# stm32-dip40.net
KiCad netlist of a schematic drawn in EAGLE
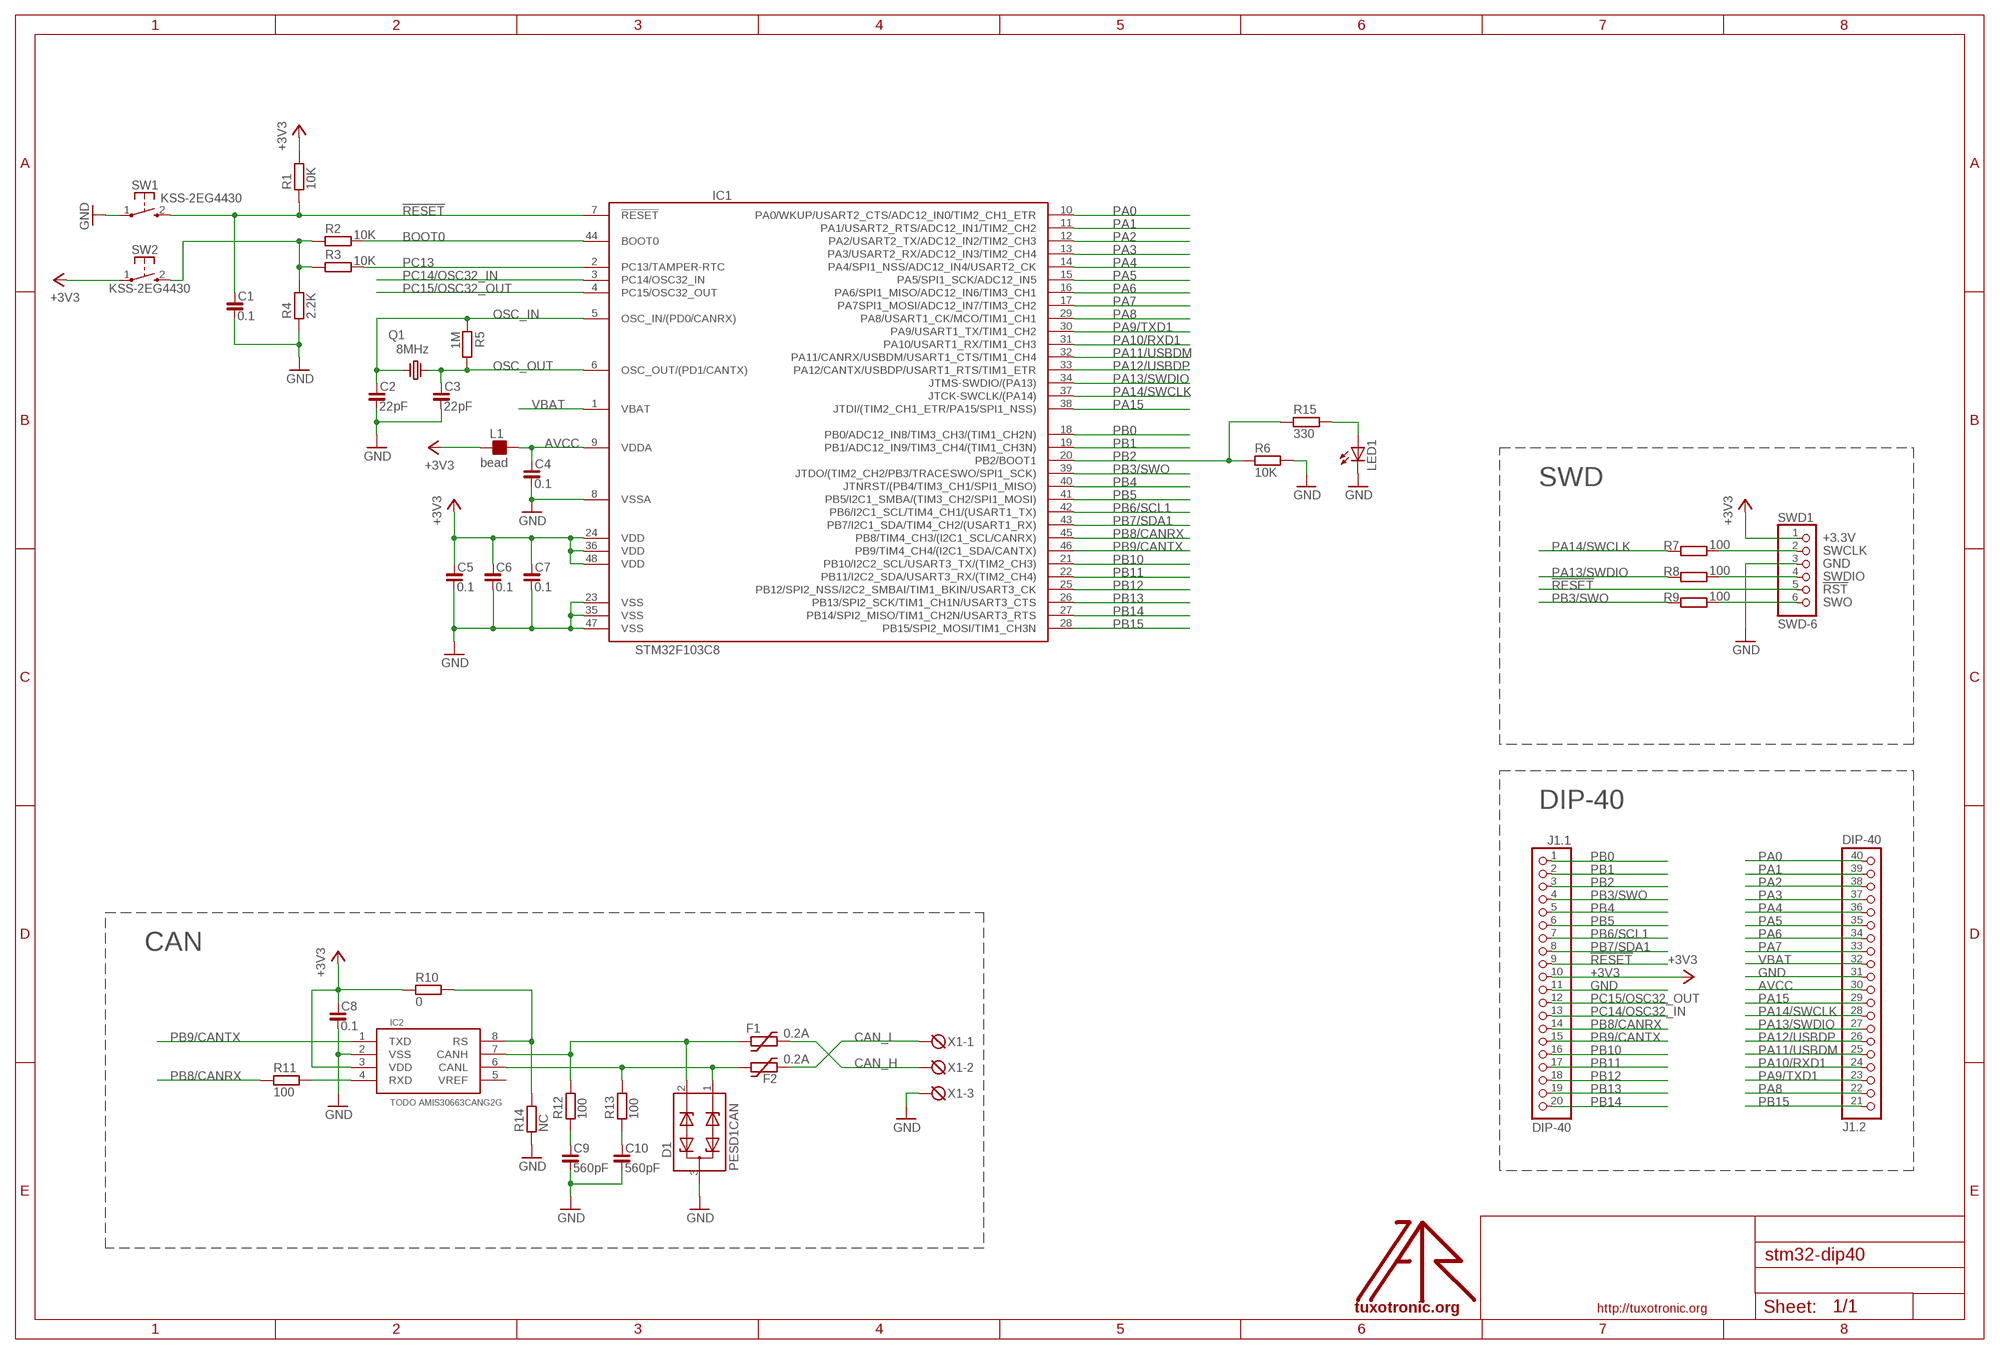
[diagram p0: schematic, sheet 1]

(export (version "E")
  (design (tool "Eeschema 10.0.6"))
  (components
    (comp (ref "C1")
      (value "0.1")
      (footprint "eagle-import:C0603")
      (libsource (lib "eagle-import") (part "C_0603"))
    )
    (comp (ref "C2")
      (value "22pF")
      (footprint "eagle-import:C0603")
      (libsource (lib "eagle-import") (part "C_0603"))
    )
    (comp (ref "C3")
      (value "22pF")
      (footprint "eagle-import:C0603")
      (libsource (lib "eagle-import") (part "C_0603"))
    )
    (comp (ref "C4")
      (value "0.1")
      (footprint "eagle-import:C0603")
      (libsource (lib "eagle-import") (part "C_0603"))
    )
    (comp (ref "C5")
      (value "0.1")
      (footprint "eagle-import:C0603")
      (libsource (lib "eagle-import") (part "C_0603"))
    )
    (comp (ref "C6")
      (value "0.1")
      (footprint "eagle-import:C0603")
      (libsource (lib "eagle-import") (part "C_0603"))
    )
    (comp (ref "C7")
      (value "0.1")
      (footprint "eagle-import:C0603")
      (libsource (lib "eagle-import") (part "C_0603"))
    )
    (comp (ref "C8")
      (value "0.1")
      (footprint "eagle-import:C0603")
      (libsource (lib "eagle-import") (part "C_0603"))
    )
    (comp (ref "C9")
      (value "560pF")
      (footprint "eagle-import:C0603")
      (libsource (lib "eagle-import") (part "C_0603"))
    )
    (comp (ref "C10")
      (value "560pF")
      (footprint "eagle-import:C0603")
      (libsource (lib "eagle-import") (part "C_0603"))
    )
    (comp (ref "D1")
      (value "PESD1CAN")
      (footprint "eagle-import:SOT23")
      (libsource (lib "eagle-import") (part "PESD1CAN"))
    )
    (comp (ref "F1")
      (value "0.2A")
      (footprint "eagle-import:1206L")
      (libsource (lib "eagle-import") (part "1206L"))
    )
    (comp (ref "F2")
      (value "0.2A")
      (footprint "eagle-import:1206L")
      (libsource (lib "eagle-import") (part "1206L"))
    )
    (comp (ref "IC1")
      (value "STM32F103C8")
      (footprint "eagle-import:LQFP48")
      (libsource (lib "eagle-import") (part "STM32F103C8"))
    )
    (comp (ref "IC2")
      (value "TODO AMIS30663CANG2G")
      (footprint "eagle-import:SO08")
      (libsource (lib "eagle-import") (part "SN65HVD230"))
    )
    (comp (ref "J1")
      (value "DIP-40")
      (footprint "eagle-import:DIP-40")
      (libsource (lib "eagle-import") (part "DIP-40"))
    )
    (comp (ref "L1")
      (value "bead")
      (footprint "eagle-import:L0603")
      (libsource (lib "eagle-import") (part "FB_0603"))
    )
    (comp (ref "LED1")
      (value "LEDCHIPLED_0603")
      (footprint "eagle-import:CHIPLED_0603")
      (libsource (lib "eagle-import") (part "LEDCHIPLED_0603"))
    )
    (comp (ref "Q1")
      (value "8MHz")
      (footprint "eagle-import:HC49_S")
      (libsource (lib "eagle-import") (part "CRYSTAL-HC49S"))
    )
    (comp (ref "R1")
      (value "10K")
      (footprint "eagle-import:R0603")
      (libsource (lib "eagle-import") (part "R_0603"))
    )
    (comp (ref "R2")
      (value "10K")
      (footprint "eagle-import:R0603")
      (libsource (lib "eagle-import") (part "R_0603"))
    )
    (comp (ref "R3")
      (value "10K")
      (footprint "eagle-import:R0603")
      (libsource (lib "eagle-import") (part "R_0603"))
    )
    (comp (ref "R4")
      (value "2.2K")
      (footprint "eagle-import:R0603")
      (libsource (lib "eagle-import") (part "R_0603"))
    )
    (comp (ref "R5")
      (value "1M")
      (footprint "eagle-import:R0603")
      (libsource (lib "eagle-import") (part "R_0603"))
    )
    (comp (ref "R6")
      (value "10K")
      (footprint "eagle-import:R0603")
      (libsource (lib "eagle-import") (part "R_0603"))
    )
    (comp (ref "R7")
      (value "100")
      (footprint "eagle-import:R0603")
      (libsource (lib "eagle-import") (part "R_0603"))
    )
    (comp (ref "R8")
      (value "100")
      (footprint "eagle-import:R0603")
      (libsource (lib "eagle-import") (part "R_0603"))
    )
    (comp (ref "R9")
      (value "100")
      (footprint "eagle-import:R0603")
      (libsource (lib "eagle-import") (part "R_0603"))
    )
    (comp (ref "R10")
      (value "0")
      (footprint "eagle-import:R0603")
      (libsource (lib "eagle-import") (part "R_0603"))
    )
    (comp (ref "R11")
      (value "100")
      (footprint "eagle-import:R0603")
      (libsource (lib "eagle-import") (part "R_0603"))
    )
    (comp (ref "R12")
      (value "100")
      (footprint "eagle-import:R0603")
      (libsource (lib "eagle-import") (part "R_0603"))
    )
    (comp (ref "R13")
      (value "100")
      (footprint "eagle-import:R0603")
      (libsource (lib "eagle-import") (part "R_0603"))
    )
    (comp (ref "R14")
      (value "NC")
      (footprint "eagle-import:R0603")
      (libsource (lib "eagle-import") (part "R_0603"))
    )
    (comp (ref "R15")
      (value "330")
      (footprint "eagle-import:R0603")
      (libsource (lib "eagle-import") (part "R_0603"))
    )
    (comp (ref "SW1")
      (value "KSS-2EG4430")
      (footprint "eagle-import:KSS-2EG4430")
      (libsource (lib "eagle-import") (part "KSS-2EG4430"))
    )
    (comp (ref "SW2")
      (value "KSS-2EG4430")
      (footprint "eagle-import:KSS-2EG4430")
      (libsource (lib "eagle-import") (part "KSS-2EG4430"))
    )
    (comp (ref "SWD1")
      (value "SWD-6")
      (footprint "eagle-import:JTAG6PIN")
      (libsource (lib "eagle-import") (part "SWD-6"))
    )
    (comp (ref "U$")
      (value "LOGO")
      (footprint "eagle-import:TT_LOGO")
      (libsource (lib "eagle-import") (part "LOGO"))
    )
    (comp (ref "X1")
      (value "DG3XX-03-3.5")
      (footprint "eagle-import:DG350-3.5-03P")
      (libsource (lib "eagle-import") (part "DG3XX-03-3.5"))
    )
  )
  (nets
    (net (code "1") (name "+3V3") (class "Default")
      (node (ref "C5") (pin "1") (pinfunction "1_1") (pintype "passive"))
      (node (ref "C6") (pin "1") (pinfunction "1_1") (pintype "passive"))
      (node (ref "C7") (pin "1") (pinfunction "1_1") (pintype "passive"))
      (node (ref "C8") (pin "1") (pinfunction "1_1") (pintype "passive"))
      (node (ref "IC1") (pin "24") (pinfunction "VDD_24") (pintype "power_in"))
      (node (ref "IC1") (pin "36") (pinfunction "VDD_36") (pintype "power_in"))
      (node (ref "IC1") (pin "48") (pinfunction "VDD_48") (pintype "power_in"))
      (node (ref "IC2") (pin "3") (pinfunction "VDD_3") (pintype "power_in"))
      (node (ref "J1") (pin "10") (pinfunction "10_10") (pintype "passive"))
      (node (ref "L1") (pin "1") (pinfunction "1_1") (pintype "passive"))
      (node (ref "R1") (pin "2") (pinfunction "2_2") (pintype "passive"))
      (node (ref "R10") (pin "1") (pinfunction "1_1") (pintype "passive"))
      (node (ref "SW2") (pin "1") (pinfunction "P_1") (pintype "passive"))
      (node (ref "SWD1") (pin "1") (pinfunction "1_1") (pintype "passive"))
    )
    (net (code "2") (name "/AVCC") (class "Default")
      (node (ref "C4") (pin "1") (pinfunction "1_1") (pintype "passive"))
      (node (ref "IC1") (pin "9") (pinfunction "VDDA_9") (pintype "power_in"))
      (node (ref "J1") (pin "30") (pinfunction "10_30") (pintype "passive"))
      (node (ref "L1") (pin "2") (pinfunction "2_2") (pintype "passive"))
    )
    (net (code "3") (name "/BOOT0") (class "Default")
      (node (ref "IC1") (pin "44") (pinfunction "BOOT0_44") (pintype "input"))
      (node (ref "R2") (pin "2") (pinfunction "2_2") (pintype "passive"))
    )
    (net (code "4") (name "/CAN_H") (class "Default")
      (node (ref "F1") (pin "P$2") (pinfunction "2_P$2") (pintype "passive"))
      (node (ref "X1") (pin "2") (pinfunction "KL_2") (pintype "passive"))
    )
    (net (code "5") (name "/CAN_L") (class "Default")
      (node (ref "F2") (pin "P$2") (pinfunction "2_P$2") (pintype "passive"))
      (node (ref "X1") (pin "1") (pinfunction "KL_1") (pintype "passive"))
    )
    (net (code "6") (name "/OSC_IN") (class "Default")
      (node (ref "C2") (pin "1") (pinfunction "1_1") (pintype "passive"))
      (node (ref "IC1") (pin "5") (pinfunction "OSC_IN/(PD0/CANRX)_5") (pintype "input"))
      (node (ref "Q1") (pin "1") (pinfunction "1_1") (pintype "passive"))
      (node (ref "R5") (pin "1") (pinfunction "1_1") (pintype "passive"))
    )
    (net (code "7") (name "/OSC_OUT") (class "Default")
      (node (ref "C3") (pin "1") (pinfunction "1_1") (pintype "passive"))
      (node (ref "IC1") (pin "6") (pinfunction "OSC_OUT/(PD1/CANTX)_6") (pintype "output"))
      (node (ref "Q1") (pin "2") (pinfunction "2_2") (pintype "passive"))
      (node (ref "R5") (pin "2") (pinfunction "2_2") (pintype "passive"))
    )
    (net (code "8") (name "/PA0") (class "Default")
      (node (ref "IC1") (pin "10") (pinfunction "PA0/WKUP/USART2_CTS/ADC12_IN0/TIM2_CH1_ETR_10") (pintype "bidirectional"))
      (node (ref "J1") (pin "40") (pinfunction "20_40") (pintype "passive"))
    )
    (net (code "9") (name "/PA1") (class "Default")
      (node (ref "IC1") (pin "11") (pinfunction "PA1/USART2_RTS/ADC12_IN1/TIM2_CH2_11") (pintype "bidirectional"))
      (node (ref "J1") (pin "39") (pinfunction "19_39") (pintype "passive"))
    )
    (net (code "10") (name "/PA2") (class "Default")
      (node (ref "IC1") (pin "12") (pinfunction "PA2/USART2_TX/ADC12_IN2/TIM2_CH3_12") (pintype "bidirectional"))
      (node (ref "J1") (pin "38") (pinfunction "18_38") (pintype "passive"))
    )
    (net (code "11") (name "/PA3") (class "Default")
      (node (ref "IC1") (pin "13") (pinfunction "PA3/USART2_RX/ADC12_IN3/TIM2_CH4_13") (pintype "bidirectional"))
      (node (ref "J1") (pin "37") (pinfunction "17_37") (pintype "passive"))
    )
    (net (code "12") (name "/PA4") (class "Default")
      (node (ref "IC1") (pin "14") (pinfunction "PA4/SPI1_NSS/ADC12_IN4/USART2_CK_14") (pintype "bidirectional"))
      (node (ref "J1") (pin "36") (pinfunction "16_36") (pintype "passive"))
    )
    (net (code "13") (name "/PA5") (class "Default")
      (node (ref "IC1") (pin "15") (pinfunction "PA5/SPI1_SCK/ADC12_IN5_15") (pintype "bidirectional"))
      (node (ref "J1") (pin "35") (pinfunction "15_35") (pintype "passive"))
    )
    (net (code "14") (name "/PA6") (class "Default")
      (node (ref "IC1") (pin "16") (pinfunction "PA6/SPI1_MISO/ADC12_IN6/TIM3_CH1_16") (pintype "bidirectional"))
      (node (ref "J1") (pin "34") (pinfunction "14_34") (pintype "passive"))
    )
    (net (code "15") (name "/PA7") (class "Default")
      (node (ref "IC1") (pin "17") (pinfunction "PA7SPI1_MOSI/ADC12_IN7/TIM3_CH2_17") (pintype "bidirectional"))
      (node (ref "J1") (pin "33") (pinfunction "13_33") (pintype "passive"))
    )
    (net (code "16") (name "/PA8") (class "Default")
      (node (ref "IC1") (pin "29") (pinfunction "PA8/USART1_CK/MCO/TIM1_CH1_29") (pintype "bidirectional"))
      (node (ref "J1") (pin "22") (pinfunction "2_22") (pintype "passive"))
    )
    (net (code "17") (name "/PA9{slash}TXD1") (class "Default")
      (node (ref "IC1") (pin "30") (pinfunction "PA9/USART1_TX/TIM1_CH2_30") (pintype "bidirectional"))
      (node (ref "J1") (pin "23") (pinfunction "3_23") (pintype "passive"))
    )
    (net (code "18") (name "/PA10{slash}RXD1") (class "Default")
      (node (ref "IC1") (pin "31") (pinfunction "PA10/USART1_RX/TIM1_CH3_31") (pintype "bidirectional"))
      (node (ref "J1") (pin "24") (pinfunction "4_24") (pintype "passive"))
    )
    (net (code "19") (name "/PA11{slash}USBDM") (class "Default")
      (node (ref "IC1") (pin "32") (pinfunction "PA11/CANRX/USBDM/USART1_CTS/TIM1_CH4_32") (pintype "bidirectional"))
      (node (ref "J1") (pin "25") (pinfunction "5_25") (pintype "passive"))
    )
    (net (code "20") (name "/PA12{slash}USBDP") (class "Default")
      (node (ref "IC1") (pin "33") (pinfunction "PA12/CANTX/USBDP/USART1_RTS/TIM1_ETR_33") (pintype "bidirectional"))
      (node (ref "J1") (pin "26") (pinfunction "6_26") (pintype "passive"))
    )
    (net (code "21") (name "/PA13{slash}SWDIO") (class "Default")
      (node (ref "IC1") (pin "34") (pinfunction "JTMS-SWDIO/(PA13)_34") (pintype "bidirectional"))
      (node (ref "J1") (pin "27") (pinfunction "7_27") (pintype "passive"))
      (node (ref "R8") (pin "1") (pinfunction "1_1") (pintype "passive"))
    )
    (net (code "22") (name "/PA14{slash}SWCLK") (class "Default")
      (node (ref "IC1") (pin "37") (pinfunction "JTCK-SWCLK/(PA14)_37") (pintype "bidirectional"))
      (node (ref "J1") (pin "28") (pinfunction "8_28") (pintype "passive"))
      (node (ref "R7") (pin "1") (pinfunction "1_1") (pintype "passive"))
    )
    (net (code "23") (name "/PA15") (class "Default")
      (node (ref "IC1") (pin "38") (pinfunction "JTDI/(TIM2_CH1_ETR/PA15/SPI1_NSS)_38") (pintype "bidirectional"))
      (node (ref "J1") (pin "29") (pinfunction "9_29") (pintype "passive"))
    )
    (net (code "24") (name "/PB0") (class "Default")
      (node (ref "IC1") (pin "18") (pinfunction "PB0/ADC12_IN8/TIM3_CH3/(TIM1_CH2N)_18") (pintype "bidirectional"))
      (node (ref "J1") (pin "1") (pinfunction "1_1") (pintype "passive"))
    )
    (net (code "25") (name "/PB1") (class "Default")
      (node (ref "IC1") (pin "19") (pinfunction "PB1/ADC12_IN9/TIM3_CH4/(TIM1_CH3N)_19") (pintype "bidirectional"))
      (node (ref "J1") (pin "2") (pinfunction "2_2") (pintype "passive"))
    )
    (net (code "26") (name "/PB2") (class "Default")
      (node (ref "IC1") (pin "20") (pinfunction "PB2/BOOT1_20") (pintype "bidirectional"))
      (node (ref "J1") (pin "3") (pinfunction "3_3") (pintype "passive"))
      (node (ref "R15") (pin "1") (pinfunction "1_1") (pintype "passive"))
      (node (ref "R6") (pin "1") (pinfunction "1_1") (pintype "passive"))
    )
    (net (code "27") (name "/PB3{slash}SWO") (class "Default")
      (node (ref "IC1") (pin "39") (pinfunction "JTDO/(TIM2_CH2/PB3/TRACESWO/SPI1_SCK)_39") (pintype "bidirectional"))
      (node (ref "J1") (pin "4") (pinfunction "4_4") (pintype "passive"))
      (node (ref "R9") (pin "1") (pinfunction "1_1") (pintype "passive"))
    )
    (net (code "28") (name "/PB4") (class "Default")
      (node (ref "IC1") (pin "40") (pinfunction "JTNRST/(PB4/TIM3_CH1/SPI1_MISO)_40") (pintype "bidirectional"))
      (node (ref "J1") (pin "5") (pinfunction "5_5") (pintype "passive"))
    )
    (net (code "29") (name "/PB5") (class "Default")
      (node (ref "IC1") (pin "41") (pinfunction "PB5/I2C1_SMBA/(TIM3_CH2/SPI1_MOSI)_41") (pintype "bidirectional"))
      (node (ref "J1") (pin "6") (pinfunction "6_6") (pintype "passive"))
    )
    (net (code "30") (name "/PB6{slash}SCL1") (class "Default")
      (node (ref "IC1") (pin "42") (pinfunction "PB6/I2C1_SCL/TIM4_CH1/(USART1_TX)_42") (pintype "bidirectional"))
      (node (ref "J1") (pin "7") (pinfunction "7_7") (pintype "passive"))
    )
    (net (code "31") (name "/PB7{slash}SDA1") (class "Default")
      (node (ref "IC1") (pin "43") (pinfunction "PB7/I2C1_SDA/TIM4_CH2/(USART1_RX)_43") (pintype "bidirectional"))
      (node (ref "J1") (pin "8") (pinfunction "8_8") (pintype "passive"))
    )
    (net (code "32") (name "/PB8{slash}CANRX") (class "Default")
      (node (ref "IC1") (pin "45") (pinfunction "PB8/TIM4_CH3/(I2C1_SCL/CANRX)_45") (pintype "bidirectional"))
      (node (ref "J1") (pin "14") (pinfunction "14_14") (pintype "passive"))
      (node (ref "R11") (pin "1") (pinfunction "1_1") (pintype "passive"))
    )
    (net (code "33") (name "/PB9{slash}CANTX") (class "Default")
      (node (ref "IC1") (pin "46") (pinfunction "PB9/TIM4_CH4/(I2C1_SDA/CANTX)_46") (pintype "bidirectional"))
      (node (ref "IC2") (pin "1") (pinfunction "TXD_1") (pintype "input"))
      (node (ref "J1") (pin "15") (pinfunction "15_15") (pintype "passive"))
    )
    (net (code "34") (name "/PB10") (class "Default")
      (node (ref "IC1") (pin "21") (pinfunction "PB10/I2C2_SCL/USART3_TX/(TIM2_CH3)_21") (pintype "bidirectional"))
      (node (ref "J1") (pin "16") (pinfunction "16_16") (pintype "passive"))
    )
    (net (code "35") (name "/PB11") (class "Default")
      (node (ref "IC1") (pin "22") (pinfunction "PB11/I2C2_SDA/USART3_RX/(TIM2_CH4)_22") (pintype "bidirectional"))
      (node (ref "J1") (pin "17") (pinfunction "17_17") (pintype "passive"))
    )
    (net (code "36") (name "/PB12") (class "Default")
      (node (ref "IC1") (pin "25") (pinfunction "PB12/SPI2_NSS/I2C2_SMBAI/TIM1_BKIN/USART3_CK_25") (pintype "bidirectional"))
      (node (ref "J1") (pin "18") (pinfunction "18_18") (pintype "passive"))
    )
    (net (code "37") (name "/PB13") (class "Default")
      (node (ref "IC1") (pin "26") (pinfunction "PB13/SPI2_SCK/TIM1_CH1N/USART3_CTS_26") (pintype "bidirectional"))
      (node (ref "J1") (pin "19") (pinfunction "19_19") (pintype "passive"))
    )
    (net (code "38") (name "/PB14") (class "Default")
      (node (ref "IC1") (pin "27") (pinfunction "PB14/SPI2_MISO/TIM1_CH2N/USART3_RTS_27") (pintype "bidirectional"))
      (node (ref "J1") (pin "20") (pinfunction "20_20") (pintype "passive"))
    )
    (net (code "39") (name "/PB15") (class "Default")
      (node (ref "IC1") (pin "28") (pinfunction "PB15/SPI2_MOSI/TIM1_CH3N_28") (pintype "bidirectional"))
      (node (ref "J1") (pin "21") (pinfunction "1_21") (pintype "passive"))
    )
    (net (code "40") (name "/PC13") (class "Default")
      (node (ref "IC1") (pin "2") (pinfunction "PC13/TAMPER-RTC_2") (pintype "bidirectional"))
      (node (ref "R3") (pin "2") (pinfunction "2_2") (pintype "passive"))
    )
    (net (code "41") (name "/PC14{slash}OSC32_IN") (class "Default")
      (node (ref "IC1") (pin "3") (pinfunction "PC14/OSC32_IN_3") (pintype "bidirectional"))
      (node (ref "J1") (pin "13") (pinfunction "13_13") (pintype "passive"))
    )
    (net (code "42") (name "/PC15{slash}OSC32_OUT") (class "Default")
      (node (ref "IC1") (pin "4") (pinfunction "PC15/OSC32_OUT_4") (pintype "bidirectional"))
      (node (ref "J1") (pin "12") (pinfunction "12_12") (pintype "passive"))
    )
    (net (code "43") (name "/VBAT") (class "Default")
      (node (ref "IC1") (pin "1") (pinfunction "VBAT_1") (pintype "power_in"))
      (node (ref "J1") (pin "32") (pinfunction "12_32") (pintype "passive"))
    )
    (net (code "44") (name "/~{RESET}") (class "Default")
      (node (ref "C1") (pin "1") (pinfunction "1_1") (pintype "passive"))
      (node (ref "IC1") (pin "7") (pinfunction "~{RESET}_7") (pintype "input"))
      (node (ref "J1") (pin "9") (pinfunction "9_9") (pintype "passive"))
      (node (ref "R1") (pin "1") (pinfunction "1_1") (pintype "passive"))
      (node (ref "SW1") (pin "2") (pinfunction "S_2") (pintype "passive"))
      (node (ref "SWD1") (pin "5") (pinfunction "5_5") (pintype "passive"))
    )
    (net (code "45") (name "GND") (class "Default")
      (node (ref "C1") (pin "2") (pinfunction "2_2") (pintype "passive"))
      (node (ref "C10") (pin "2") (pinfunction "2_2") (pintype "passive"))
      (node (ref "C2") (pin "2") (pinfunction "2_2") (pintype "passive"))
      (node (ref "C3") (pin "2") (pinfunction "2_2") (pintype "passive"))
      (node (ref "C4") (pin "2") (pinfunction "2_2") (pintype "passive"))
      (node (ref "C5") (pin "2") (pinfunction "2_2") (pintype "passive"))
      (node (ref "C6") (pin "2") (pinfunction "2_2") (pintype "passive"))
      (node (ref "C7") (pin "2") (pinfunction "2_2") (pintype "passive"))
      (node (ref "C8") (pin "2") (pinfunction "2_2") (pintype "passive"))
      (node (ref "C9") (pin "2") (pinfunction "2_2") (pintype "passive"))
      (node (ref "D1") (pin "3") (pinfunction "3_3") (pintype "passive"))
      (node (ref "IC1") (pin "23") (pinfunction "VSS_23") (pintype "power_in"))
      (node (ref "IC1") (pin "35") (pinfunction "VSS_35") (pintype "power_in"))
      (node (ref "IC1") (pin "47") (pinfunction "VSS_47") (pintype "power_in"))
      (node (ref "IC1") (pin "8") (pinfunction "VSSA_8") (pintype "power_in"))
      (node (ref "IC2") (pin "2") (pinfunction "VSS_2") (pintype "power_in"))
      (node (ref "J1") (pin "11") (pinfunction "11_11") (pintype "passive"))
      (node (ref "J1") (pin "31") (pinfunction "11_31") (pintype "passive"))
      (node (ref "LED1") (pin "C") (pinfunction "C_C") (pintype "passive"))
      (node (ref "R14") (pin "1") (pinfunction "1_1") (pintype "passive"))
      (node (ref "R4") (pin "1") (pinfunction "1_1") (pintype "passive"))
      (node (ref "R6") (pin "2") (pinfunction "2_2") (pintype "passive"))
      (node (ref "SW1") (pin "1") (pinfunction "P_1") (pintype "passive"))
      (node (ref "SWD1") (pin "3") (pinfunction "3_3") (pintype "passive"))
      (node (ref "X1") (pin "3") (pinfunction "KL_3") (pintype "passive"))
    )
    (net (code "46") (name "Net-(C9-Pad1)") (class "Default")
      (node (ref "C9") (pin "1") (pinfunction "1_1") (pintype "passive"))
      (node (ref "R12") (pin "1") (pinfunction "1_1") (pintype "passive"))
    )
    (net (code "47") (name "Net-(C10-Pad1)") (class "Default")
      (node (ref "C10") (pin "1") (pinfunction "1_1") (pintype "passive"))
      (node (ref "R13") (pin "1") (pinfunction "1_1") (pintype "passive"))
    )
    (net (code "48") (name "Net-(F1-1)") (class "Default")
      (node (ref "D1") (pin "2") (pinfunction "2_2") (pintype "passive"))
      (node (ref "F1") (pin "P$1") (pinfunction "1_P$1") (pintype "passive"))
      (node (ref "IC2") (pin "7") (pinfunction "CANH_7") (pintype "bidirectional"))
      (node (ref "R12") (pin "2") (pinfunction "2_2") (pintype "passive"))
    )
    (net (code "49") (name "Net-(F2-1)") (class "Default")
      (node (ref "D1") (pin "1") (pinfunction "1_1") (pintype "passive"))
      (node (ref "F2") (pin "P$1") (pinfunction "1_P$1") (pintype "passive"))
      (node (ref "IC2") (pin "6") (pinfunction "CANL_6") (pintype "bidirectional"))
      (node (ref "R13") (pin "2") (pinfunction "2_2") (pintype "passive"))
    )
    (net (code "50") (name "Net-(IC2-RS)") (class "Default")
      (node (ref "IC2") (pin "8") (pinfunction "RS_8") (pintype "input"))
      (node (ref "R10") (pin "2") (pinfunction "2_2") (pintype "passive"))
      (node (ref "R14") (pin "2") (pinfunction "2_2") (pintype "passive"))
    )
    (net (code "51") (name "Net-(IC2-RXD)") (class "Default")
      (node (ref "IC2") (pin "4") (pinfunction "RXD_4") (pintype "output"))
      (node (ref "R11") (pin "2") (pinfunction "2_2") (pintype "passive"))
    )
    (net (code "52") (name "Net-(LED1-PadA)") (class "Default")
      (node (ref "LED1") (pin "A") (pinfunction "A_A") (pintype "passive"))
      (node (ref "R15") (pin "2") (pinfunction "2_2") (pintype "passive"))
    )
    (net (code "53") (name "Net-(R7-Pad2)") (class "Default")
      (node (ref "R7") (pin "2") (pinfunction "2_2") (pintype "passive"))
      (node (ref "SWD1") (pin "2") (pinfunction "2_2") (pintype "passive"))
    )
    (net (code "54") (name "Net-(R8-Pad2)") (class "Default")
      (node (ref "R8") (pin "2") (pinfunction "2_2") (pintype "passive"))
      (node (ref "SWD1") (pin "4") (pinfunction "4_4") (pintype "passive"))
    )
    (net (code "55") (name "Net-(R9-Pad2)") (class "Default")
      (node (ref "R9") (pin "2") (pinfunction "2_2") (pintype "passive"))
      (node (ref "SWD1") (pin "6") (pinfunction "6_6") (pintype "passive"))
    )
    (net (code "56") (name "Net-(SW2-S)") (class "Default")
      (node (ref "R2") (pin "1") (pinfunction "1_1") (pintype "passive"))
      (node (ref "R3") (pin "1") (pinfunction "1_1") (pintype "passive"))
      (node (ref "R4") (pin "2") (pinfunction "2_2") (pintype "passive"))
      (node (ref "SW2") (pin "2") (pinfunction "S_2") (pintype "passive"))
    )
    (net (code "57") (name "unconnected-(IC2-VREF-Pad5)") (class "Default")
      (node (ref "IC2") (pin "5") (pinfunction "VREF_5") (pintype "passive"))
    )
  )
)
